# Analog-Multiplier.net
KiCad netlist of a schematic drawn in Altium Designer
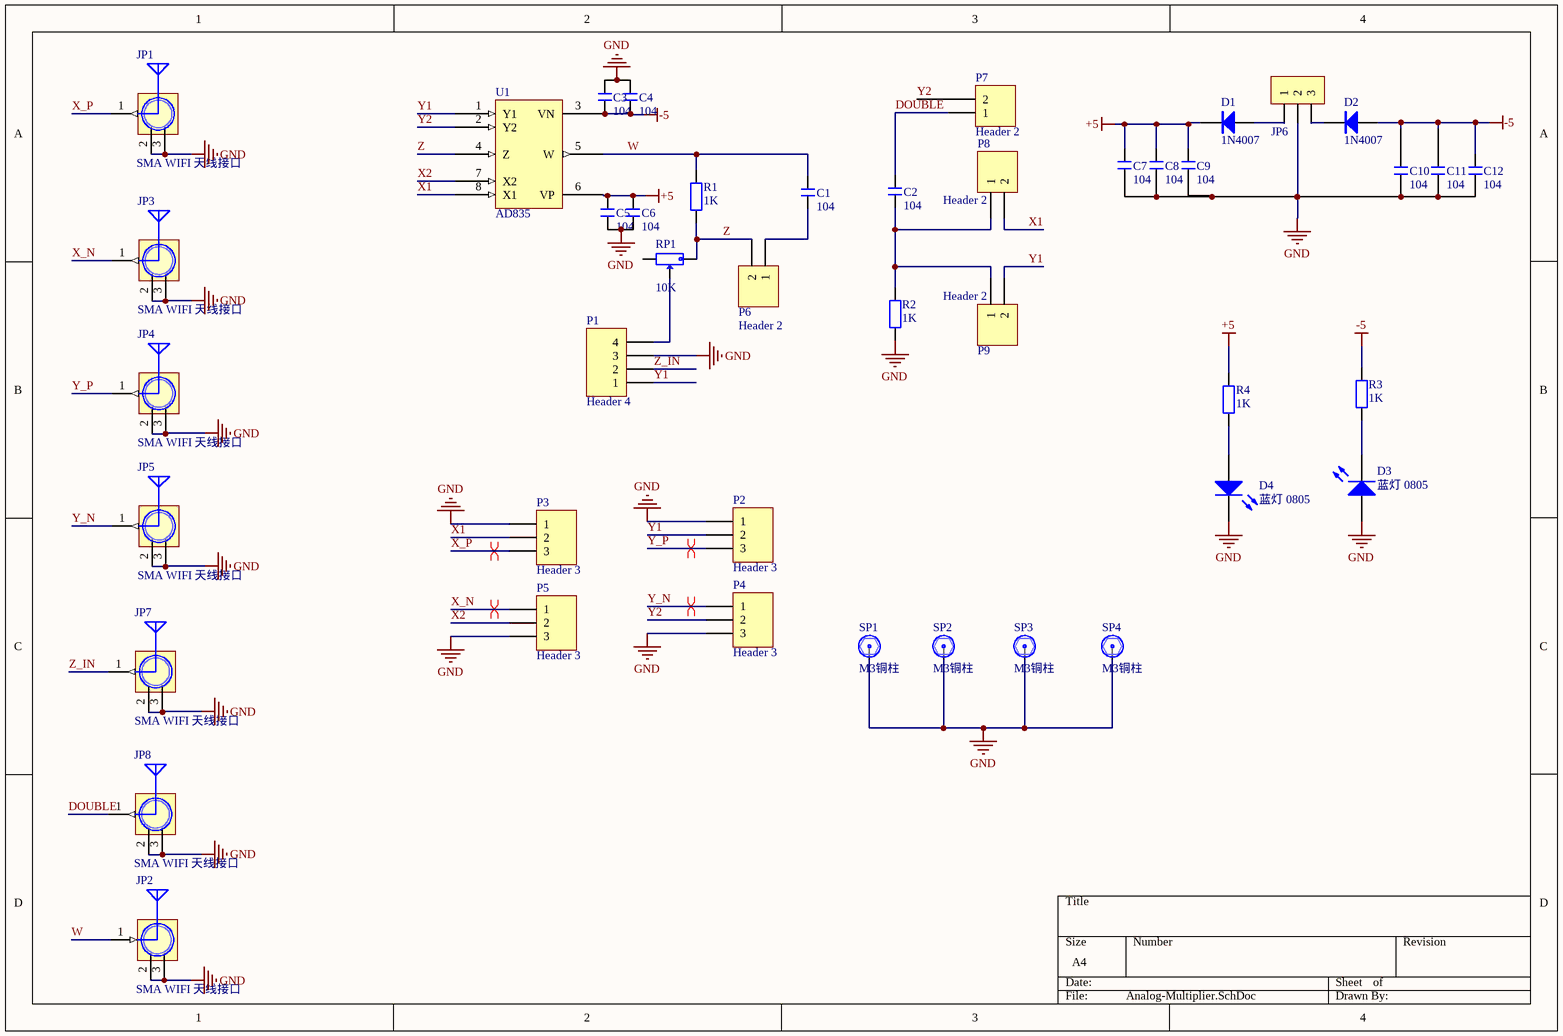
[diagram p0: Analog-Multiplier.SchDoc]

(export (version "E")
  (design (tool "Eeschema 10.0.6"))
  (components
    (comp (ref "C1")
      (value "104")
      (footprint "C 0805_L")
      (description "无极性贴片电容")
      (libsource (lib "电容-电阻-电感-电位器") (part "C"))
    )
    (comp (ref "C2")
      (value "104")
      (footprint "C 0805_L")
      (description "无极性贴片电容")
      (libsource (lib "电容-电阻-电感-电位器") (part "C"))
    )
    (comp (ref "C3")
      (value "104")
      (footprint "C 0805_L")
      (description "无极性贴片电容")
      (libsource (lib "电容-电阻-电感-电位器") (part "C"))
    )
    (comp (ref "C4")
      (value "104")
      (footprint "C 0805_L")
      (description "无极性贴片电容")
      (libsource (lib "电容-电阻-电感-电位器") (part "C"))
    )
    (comp (ref "C5")
      (value "104")
      (footprint "C 0805_L")
      (description "无极性贴片电容")
      (libsource (lib "电容-电阻-电感-电位器") (part "C"))
    )
    (comp (ref "C6")
      (value "104")
      (footprint "C 0805_L")
      (description "无极性贴片电容")
      (libsource (lib "电容-电阻-电感-电位器") (part "C"))
    )
    (comp (ref "C7")
      (value "104")
      (footprint "C 1206_L")
      (description "无极性贴片电容")
      (libsource (lib "电容-电阻-电感-电位器") (part "C"))
    )
    (comp (ref "C8")
      (value "104")
      (footprint "C 1206_L")
      (description "无极性贴片电容")
      (libsource (lib "电容-电阻-电感-电位器") (part "C"))
    )
    (comp (ref "C9")
      (value "104")
      (footprint "C 1206_L")
      (description "无极性贴片电容")
      (libsource (lib "电容-电阻-电感-电位器") (part "C"))
    )
    (comp (ref "C10")
      (value "104")
      (footprint "C 1206_L")
      (description "无极性贴片电容")
      (libsource (lib "电容-电阻-电感-电位器") (part "C"))
    )
    (comp (ref "C11")
      (value "104")
      (footprint "C 1206_L")
      (description "无极性贴片电容")
      (libsource (lib "电容-电阻-电感-电位器") (part "C"))
    )
    (comp (ref "C12")
      (value "104")
      (footprint "C 1206_L")
      (description "无极性贴片电容")
      (libsource (lib "电容-电阻-电感-电位器") (part "C"))
    )
    (comp (ref "D1")
      (value "1N4007")
      (footprint "SMA")
      (description "整流二极管")
      (libsource (lib "二极管-整流桥") (part "1N4007"))
    )
    (comp (ref "D2")
      (value "1N4007")
      (footprint "SMA")
      (description "整流二极管")
      (libsource (lib "二极管-整流桥") (part "1N4007"))
    )
    (comp (ref "D3")
      (value "蓝灯 0805")
      (footprint "0805_LED_S1")
      (description "发光二极管")
      (libsource (lib "Miscellaneous Devices LC") (part "0805 蓝灯"))
    )
    (comp (ref "D4")
      (value "蓝灯 0805")
      (footprint "0805_LED_S1")
      (description "发光二极管")
      (libsource (lib "Miscellaneous Devices LC") (part "0805 蓝灯"))
    )
    (comp (ref "JP1")
      (value "SMA WIFI 天线接口")
      (footprint "SMA-KE")
      (description "SMA-2.4G射频天线接口")
      (libsource (lib "天线") (part "SMA"))
    )
    (comp (ref "JP2")
      (value "SMA WIFI 天线接口")
      (footprint "SMA-KE")
      (description "SMA-2.4G射频天线接口")
      (libsource (lib "天线") (part "SMA"))
    )
    (comp (ref "JP3")
      (value "SMA WIFI 天线接口")
      (footprint "SMA-KE")
      (description "SMA-2.4G射频天线接口")
      (libsource (lib "天线") (part "SMA"))
    )
    (comp (ref "JP4")
      (value "SMA WIFI 天线接口")
      (footprint "SMA-KE")
      (description "SMA-2.4G射频天线接口")
      (libsource (lib "天线") (part "SMA"))
    )
    (comp (ref "JP5")
      (value "SMA WIFI 天线接口")
      (footprint "SMA-KE")
      (description "SMA-2.4G射频天线接口")
      (libsource (lib "天线") (part "SMA"))
    )
    (comp (ref "JP6")
      (value "HDR-1X3")
      (footprint "XH2.54-WS-3P")
      (description "3P接插件")
      (libsource (lib "XH2.54") (part "Header 3"))
    )
    (comp (ref "JP7")
      (value "SMA WIFI 天线接口")
      (footprint "SMA-KE")
      (description "SMA-2.4G射频天线接口")
      (libsource (lib "天线") (part "SMA"))
    )
    (comp (ref "JP8")
      (value "SMA WIFI 天线接口")
      (footprint "SMA-KE")
      (description "SMA-2.4G射频天线接口")
      (libsource (lib "天线") (part "SMA"))
    )
    (comp (ref "P1")
      (value "Header 4")
      (footprint "Cross4")
      (description "Header, 4-Pin")
      (fields (field (name "PUBLISHER") "Altium Limited"))
      (libsource (lib "Miscellaneous Connectors") (part "Header 4"))
    )
    (comp (ref "P2")
      (value "Header 3")
      (footprint "HDR2.54-LI-3P")
      (description "Header, 3-Pin")
      (fields (field (name "PUBLISHER") "Altium Limited"))
      (libsource (lib "Miscellaneous Connectors") (part "Header 3"))
    )
    (comp (ref "P3")
      (value "Header 3")
      (footprint "HDR2.54-LI-3P")
      (description "Header, 3-Pin")
      (fields (field (name "PUBLISHER") "Altium Limited"))
      (libsource (lib "Miscellaneous Connectors") (part "Header 3"))
    )
    (comp (ref "P4")
      (value "Header 3")
      (footprint "HDR2.54-LI-3P")
      (description "Header, 3-Pin")
      (fields (field (name "PUBLISHER") "Altium Limited"))
      (libsource (lib "Miscellaneous Connectors") (part "Header 3"))
    )
    (comp (ref "P5")
      (value "Header 3")
      (footprint "HDR2.54-LI-3P")
      (description "Header, 3-Pin")
      (fields (field (name "PUBLISHER") "Altium Limited"))
      (libsource (lib "Miscellaneous Connectors") (part "Header 3"))
    )
    (comp (ref "P6")
      (value "Header 2")
      (footprint "HDR2.54-LI-2P")
      (description "Header, 2-Pin")
      (fields (field (name "PUBLISHER") "Altium Limited"))
      (libsource (lib "") (part "Header 2_1"))
    )
    (comp (ref "P7")
      (value "Header 2")
      (footprint "HDR2.54-LI-2P")
      (description "Header, 2-Pin")
      (fields (field (name "PUBLISHER") "Altium Limited"))
      (libsource (lib "") (part "Header 2_2"))
    )
    (comp (ref "P8")
      (value "Header 2")
      (footprint "HDR2.54-LI-2P")
      (description "Header, 2-Pin")
      (fields (field (name "PUBLISHER") "Altium Limited"))
      (libsource (lib "") (part "Header 2_2"))
    )
    (comp (ref "P9")
      (value "Header 2")
      (footprint "HDR2.54-LI-2P")
      (description "Header, 2-Pin")
      (fields (field (name "PUBLISHER") "Altium Limited"))
      (libsource (lib "Miscellaneous Connectors") (part "Header 2"))
    )
    (comp (ref "R1")
      (value "1K")
      (footprint "R 0805_L")
      (description "贴片电阻")
      (libsource (lib "电容-电阻-电感-电位器") (part "R"))
    )
    (comp (ref "R2")
      (value "1K")
      (footprint "R 0805_L")
      (description "贴片电阻")
      (libsource (lib "电容-电阻-电感-电位器") (part "R"))
    )
    (comp (ref "R3")
      (value "1K")
      (footprint "R 0805_L")
      (description "贴片电阻")
      (libsource (lib "电容-电阻-电感-电位器") (part "R"))
    )
    (comp (ref "R4")
      (value "1K")
      (footprint "R 0805_L")
      (description "贴片电阻")
      (libsource (lib "电容-电阻-电感-电位器") (part "R"))
    )
    (comp (ref "RP1")
      (value "10K")
      (footprint "3296W")
      (description "贴片电位器")
      (libsource (lib "电容-电阻-电感-电位器") (part "RP-SMD"))
    )
    (comp (ref "SP1")
      (value "M3铜柱")
      (footprint "M3x4_L")
      (description "铜柱")
      (libsource (lib "铜柱-测试点-电池座-蜂鸣器") (part "铜柱小焊盘"))
    )
    (comp (ref "SP2")
      (value "M3铜柱")
      (footprint "M3x4_L")
      (description "铜柱")
      (libsource (lib "铜柱-测试点-电池座-蜂鸣器") (part "铜柱小焊盘"))
    )
    (comp (ref "SP3")
      (value "M3铜柱")
      (footprint "M3x4_L")
      (description "铜柱")
      (libsource (lib "铜柱-测试点-电池座-蜂鸣器") (part "铜柱小焊盘"))
    )
    (comp (ref "SP4")
      (value "M3铜柱")
      (footprint "M3x4_L")
      (description "铜柱")
      (libsource (lib "铜柱-测试点-电池座-蜂鸣器") (part "铜柱小焊盘"))
    )
    (comp (ref "U1") (value "AD835") (footprint "SOP8_N") (libsource (lib "Schlib1") (part "AD835")))
  )
  (nets
    (net (code "1") (name "+5") (class "Default")
      (node (ref "C5") (pin "2") (pinfunction "2_2") (pintype "passive"))
      (node (ref "C6") (pin "2") (pinfunction "2_2") (pintype "passive"))
      (node (ref "C7") (pin "2") (pinfunction "2_2") (pintype "passive"))
      (node (ref "C8") (pin "2") (pinfunction "2_2") (pintype "passive"))
      (node (ref "C9") (pin "2") (pinfunction "2_2") (pintype "passive"))
      (node (ref "D1") (pin "2") (pinfunction "K_2") (pintype "passive"))
      (node (ref "R4") (pin "2") (pinfunction "2_2") (pintype "passive"))
      (node (ref "U1") (pin "6") (pinfunction "VP_6") (pintype "power_in"))
    )
    (net (code "2") (name "-5") (class "Default")
      (node (ref "C10") (pin "2") (pinfunction "2_2") (pintype "passive"))
      (node (ref "C11") (pin "2") (pinfunction "2_2") (pintype "passive"))
      (node (ref "C12") (pin "2") (pinfunction "2_2") (pintype "passive"))
      (node (ref "C3") (pin "2") (pinfunction "2_2") (pintype "passive"))
      (node (ref "C4") (pin "2") (pinfunction "2_2") (pintype "passive"))
      (node (ref "D2") (pin "1") (pinfunction "A_1") (pintype "passive"))
      (node (ref "R3") (pin "2") (pinfunction "2_2") (pintype "passive"))
      (node (ref "U1") (pin "3") (pinfunction "VN_3") (pintype "power_in"))
    )
    (net (code "3") (name "/DOUBLE") (class "Default")
      (node (ref "C2") (pin "2") (pinfunction "2_2") (pintype "passive"))
      (node (ref "JP8") (pin "1") (pinfunction "ANT_1") (pintype "output"))
      (node (ref "P7") (pin "1") (pinfunction "1_1") (pintype "passive"))
    )
    (net (code "4") (name "/W") (class "Default")
      (node (ref "C1") (pin "2") (pinfunction "2_2") (pintype "passive"))
      (node (ref "JP2") (pin "1") (pinfunction "ANT_1") (pintype "output"))
      (node (ref "R1") (pin "2") (pinfunction "2_2") (pintype "passive"))
      (node (ref "U1") (pin "5") (pinfunction "W_5") (pintype "output"))
    )
    (net (code "5") (name "/X1") (class "Default")
      (node (ref "P3") (pin "2") (pinfunction "2_2") (pintype "passive"))
      (node (ref "P8") (pin "2") (pinfunction "2_2") (pintype "passive"))
      (node (ref "U1") (pin "8") (pinfunction "X1_8") (pintype "input"))
    )
    (net (code "6") (name "/X2") (class "Default")
      (node (ref "P5") (pin "2") (pinfunction "2_2") (pintype "passive"))
      (node (ref "U1") (pin "7") (pinfunction "X2_7") (pintype "input"))
    )
    (net (code "7") (name "/X_N") (class "Default")
      (node (ref "JP3") (pin "1") (pinfunction "ANT_1") (pintype "output"))
      (node (ref "P5") (pin "1") (pinfunction "1_1") (pintype "passive"))
    )
    (net (code "8") (name "/X_P") (class "Default")
      (node (ref "JP1") (pin "1") (pinfunction "ANT_1") (pintype "output"))
      (node (ref "P3") (pin "3") (pinfunction "3_3") (pintype "passive"))
    )
    (net (code "9") (name "/Y1") (class "Default")
      (node (ref "P1") (pin "1") (pinfunction "1_1") (pintype "passive"))
      (node (ref "P2") (pin "2") (pinfunction "2_2") (pintype "passive"))
      (node (ref "P9") (pin "2") (pinfunction "2_2") (pintype "passive"))
      (node (ref "U1") (pin "1") (pinfunction "Y1_1") (pintype "input"))
    )
    (net (code "10") (name "/Y2") (class "Default")
      (node (ref "P4") (pin "2") (pinfunction "2_2") (pintype "passive"))
      (node (ref "P7") (pin "2") (pinfunction "2_2") (pintype "passive"))
      (node (ref "U1") (pin "2") (pinfunction "Y2_2") (pintype "input"))
    )
    (net (code "11") (name "/Y_N") (class "Default")
      (node (ref "JP5") (pin "1") (pinfunction "ANT_1") (pintype "output"))
      (node (ref "P4") (pin "1") (pinfunction "1_1") (pintype "passive"))
    )
    (net (code "12") (name "/Y_P") (class "Default")
      (node (ref "JP4") (pin "1") (pinfunction "ANT_1") (pintype "output"))
      (node (ref "P2") (pin "3") (pinfunction "3_3") (pintype "passive"))
    )
    (net (code "13") (name "/Z") (class "Default")
      (node (ref "P6") (pin "2") (pinfunction "2_2") (pintype "passive"))
      (node (ref "R1") (pin "1") (pinfunction "1_1") (pintype "passive"))
      (node (ref "RP1") (pin "1") (pinfunction "1_1") (pintype "passive"))
      (node (ref "U1") (pin "4") (pinfunction "Z_4") (pintype "input"))
    )
    (net (code "14") (name "/Z_IN") (class "Default")
      (node (ref "JP7") (pin "1") (pinfunction "ANT_1") (pintype "output"))
      (node (ref "P1") (pin "2") (pinfunction "2_2") (pintype "passive"))
    )
    (net (code "15") (name "GND") (class "Default")
      (node (ref "C10") (pin "1") (pinfunction "1_1") (pintype "passive"))
      (node (ref "C11") (pin "1") (pinfunction "1_1") (pintype "passive"))
      (node (ref "C12") (pin "1") (pinfunction "1_1") (pintype "passive"))
      (node (ref "C3") (pin "1") (pinfunction "1_1") (pintype "passive"))
      (node (ref "C4") (pin "1") (pinfunction "1_1") (pintype "passive"))
      (node (ref "C5") (pin "1") (pinfunction "1_1") (pintype "passive"))
      (node (ref "C6") (pin "1") (pinfunction "1_1") (pintype "passive"))
      (node (ref "C7") (pin "1") (pinfunction "1_1") (pintype "passive"))
      (node (ref "C8") (pin "1") (pinfunction "1_1") (pintype "passive"))
      (node (ref "C9") (pin "1") (pinfunction "1_1") (pintype "passive"))
      (node (ref "D3") (pin "A") (pinfunction "A_A") (pintype "passive"))
      (node (ref "D4") (pin "K") (pinfunction "K_K") (pintype "passive"))
      (node (ref "JP1") (pin "2") (pinfunction "GND_2") (pintype "passive"))
      (node (ref "JP1") (pin "3") (pinfunction "GND_3") (pintype "passive"))
      (node (ref "JP2") (pin "2") (pinfunction "GND_2") (pintype "passive"))
      (node (ref "JP2") (pin "3") (pinfunction "GND_3") (pintype "passive"))
      (node (ref "JP3") (pin "2") (pinfunction "GND_2") (pintype "passive"))
      (node (ref "JP3") (pin "3") (pinfunction "GND_3") (pintype "passive"))
      (node (ref "JP4") (pin "2") (pinfunction "GND_2") (pintype "passive"))
      (node (ref "JP4") (pin "3") (pinfunction "GND_3") (pintype "passive"))
      (node (ref "JP5") (pin "2") (pinfunction "GND_2") (pintype "passive"))
      (node (ref "JP5") (pin "3") (pinfunction "GND_3") (pintype "passive"))
      (node (ref "JP6") (pin "2") (pinfunction "2_2") (pintype "passive"))
      (node (ref "JP7") (pin "2") (pinfunction "GND_2") (pintype "passive"))
      (node (ref "JP7") (pin "3") (pinfunction "GND_3") (pintype "passive"))
      (node (ref "JP8") (pin "2") (pinfunction "GND_2") (pintype "passive"))
      (node (ref "JP8") (pin "3") (pinfunction "GND_3") (pintype "passive"))
      (node (ref "P1") (pin "3") (pinfunction "3_3") (pintype "passive"))
      (node (ref "P2") (pin "1") (pinfunction "1_1") (pintype "passive"))
      (node (ref "P3") (pin "1") (pinfunction "1_1") (pintype "passive"))
      (node (ref "P4") (pin "3") (pinfunction "3_3") (pintype "passive"))
      (node (ref "P5") (pin "3") (pinfunction "3_3") (pintype "passive"))
      (node (ref "R2") (pin "1") (pinfunction "1_1") (pintype "passive"))
      (node (ref "SP1") (pin "1") (pinfunction "1_1") (pintype "passive"))
      (node (ref "SP2") (pin "1") (pinfunction "1_1") (pintype "passive"))
      (node (ref "SP3") (pin "1") (pinfunction "1_1") (pintype "passive"))
      (node (ref "SP4") (pin "1") (pinfunction "1_1") (pintype "passive"))
    )
    (net (code "16") (name "Net-(C1-Pad1)") (class "Default")
      (node (ref "C1") (pin "1") (pinfunction "1_1") (pintype "passive"))
      (node (ref "P6") (pin "1") (pinfunction "1_1") (pintype "passive"))
    )
    (net (code "17") (name "Net-(C2-Pad1)") (class "Default")
      (node (ref "C2") (pin "1") (pinfunction "1_1") (pintype "passive"))
      (node (ref "P8") (pin "1") (pinfunction "1_1") (pintype "passive"))
      (node (ref "P9") (pin "1") (pinfunction "1_1") (pintype "passive"))
      (node (ref "R2") (pin "2") (pinfunction "2_2") (pintype "passive"))
    )
    (net (code "18") (name "Net-(D1-A)") (class "Default")
      (node (ref "D1") (pin "1") (pinfunction "A_1") (pintype "passive"))
      (node (ref "JP6") (pin "1") (pinfunction "1_1") (pintype "passive"))
    )
    (net (code "19") (name "Net-(D2-K)") (class "Default")
      (node (ref "D2") (pin "2") (pinfunction "K_2") (pintype "passive"))
      (node (ref "JP6") (pin "3") (pinfunction "3_3") (pintype "passive"))
    )
    (net (code "20") (name "Net-(D3-PadK)") (class "Default")
      (node (ref "D3") (pin "K") (pinfunction "K_K") (pintype "passive"))
      (node (ref "R3") (pin "1") (pinfunction "1_1") (pintype "passive"))
    )
    (net (code "21") (name "Net-(D4-PadA)") (class "Default")
      (node (ref "D4") (pin "A") (pinfunction "A_A") (pintype "passive"))
      (node (ref "R4") (pin "1") (pinfunction "1_1") (pintype "passive"))
    )
    (net (code "22") (name "Net-(P1-Pad4)") (class "Default")
      (node (ref "P1") (pin "4") (pinfunction "4_4") (pintype "passive"))
      (node (ref "RP1") (pin "2") (pinfunction "2_2") (pintype "passive"))
    )
    (net (code "23") (name "unconnected-(RP1-Pad3)") (class "Default")
      (node (ref "RP1") (pin "3") (pinfunction "3_3") (pintype "passive"))
    )
  )
)
